# R3S602.net
KiCad netlist of a schematic drawn in Altium Designer
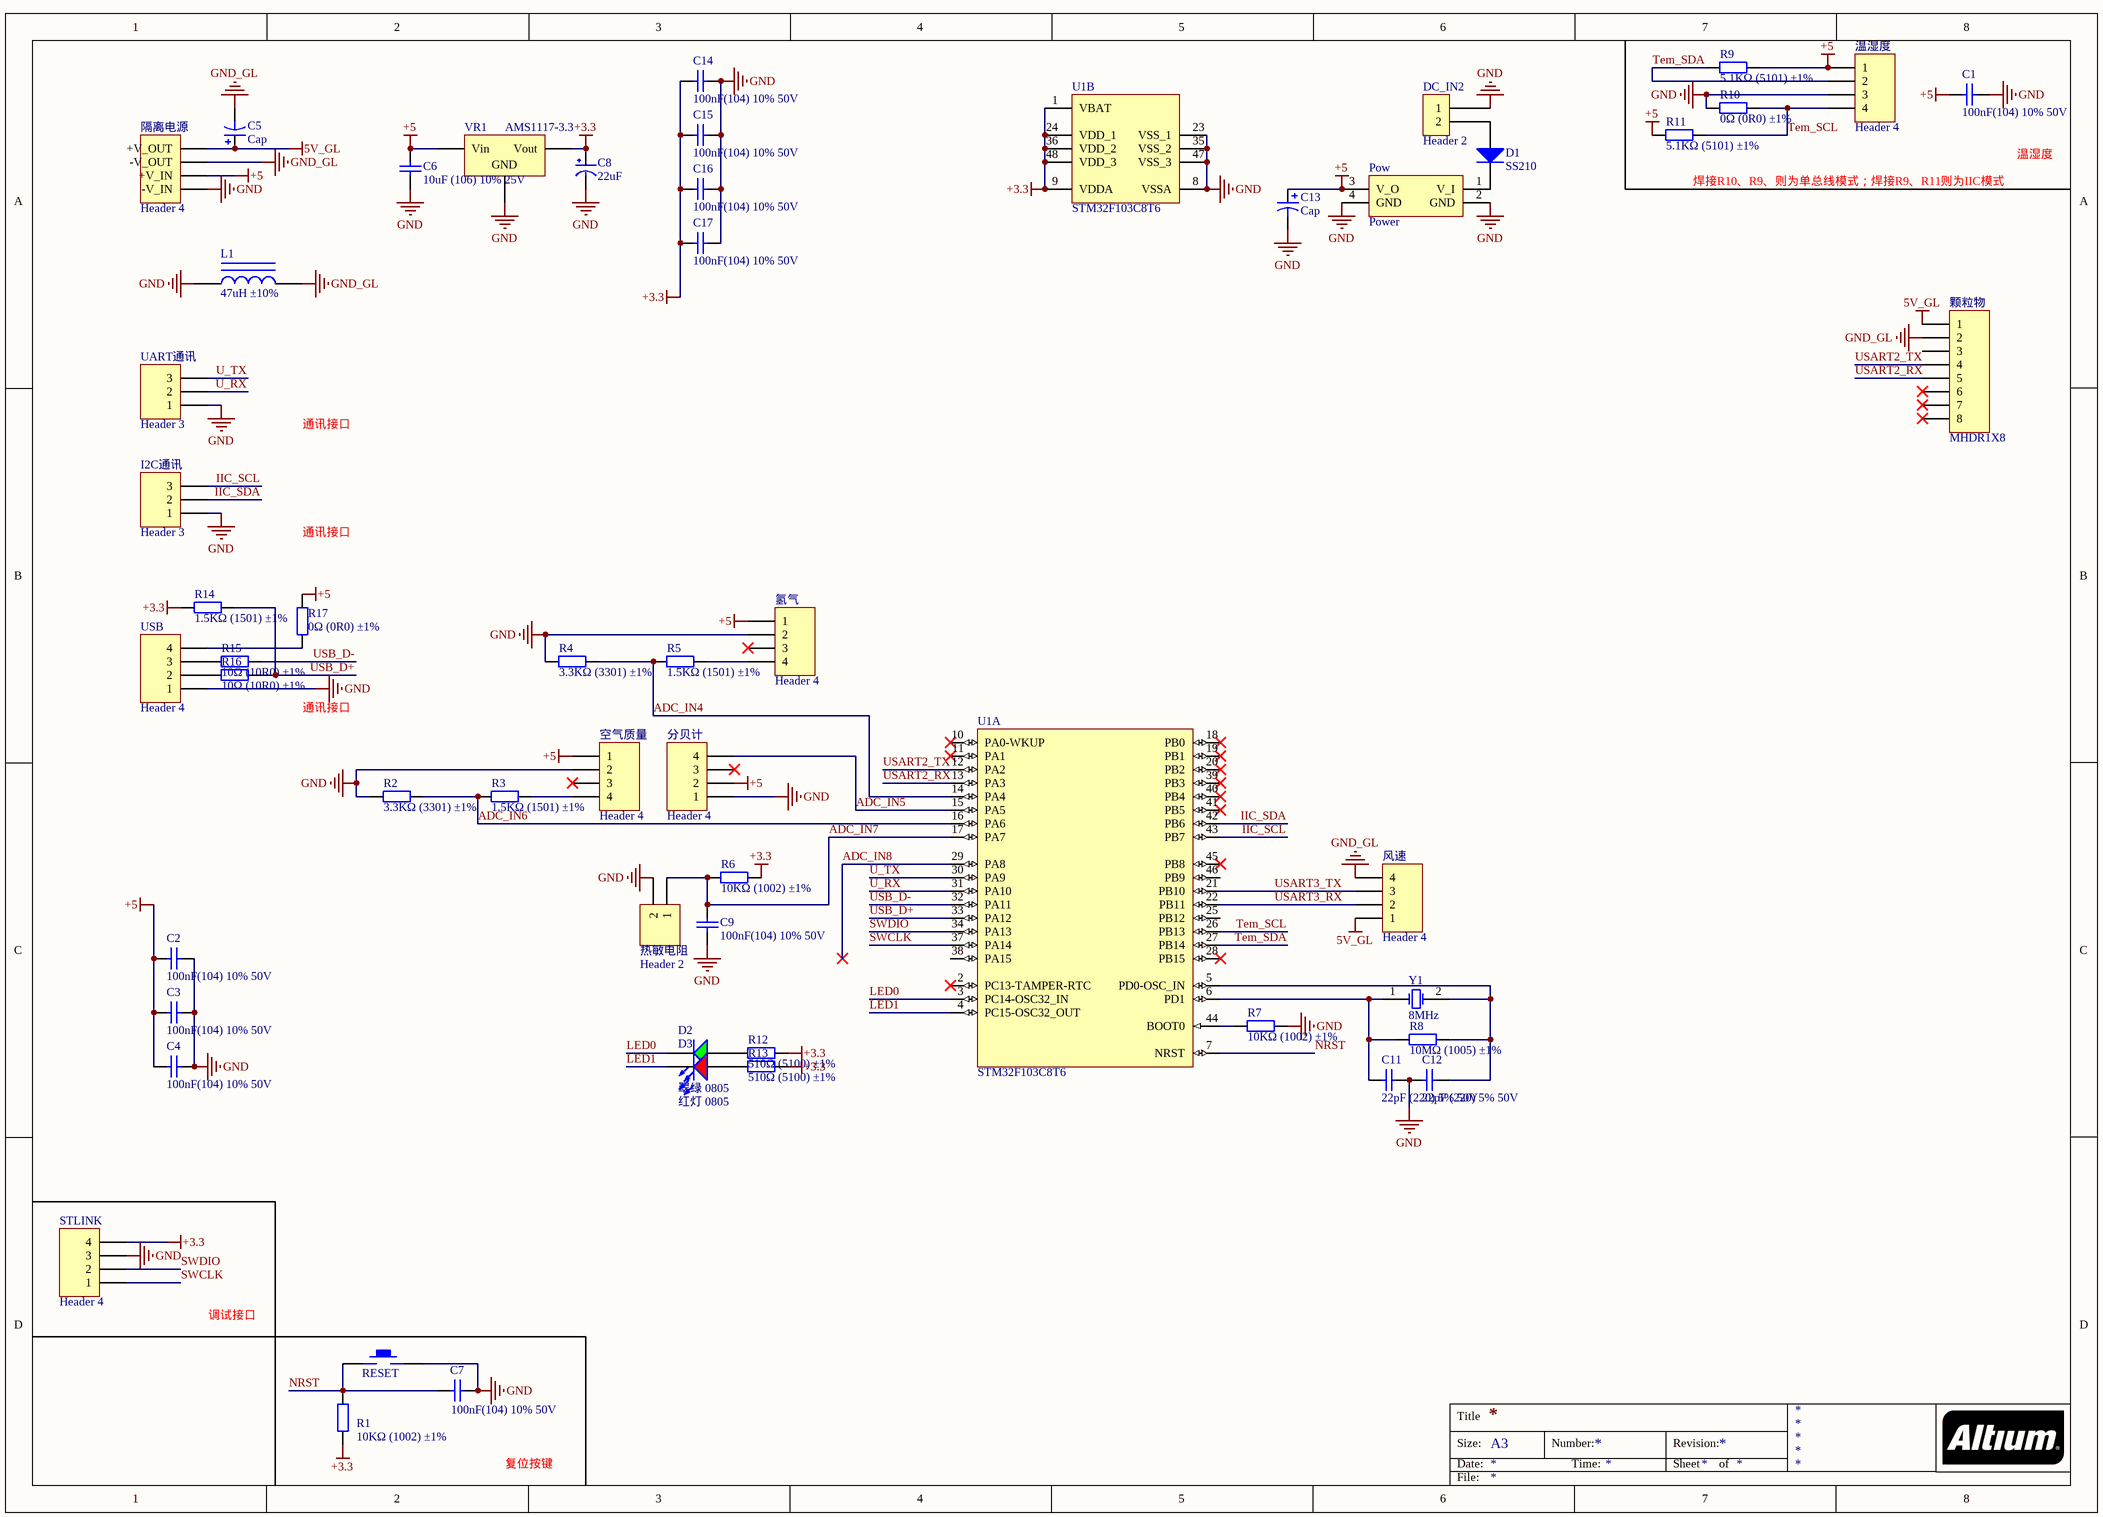
[diagram p0: R3S602.SchDoc]

(export (version "E")
  (design (tool "Eeschema 10.0.6"))
  (components
    (comp (ref "C1")
      (value "100nF(104) 10% 50V")
      (footprint "LC-0805_C")
      (description "贴片电容")
      (libsource (lib "Miscellaneous Devices LC") (part "0805 100nF(104) 10% 50V"))
    )
    (comp (ref "C2")
      (value "100nF(104) 10% 50V")
      (footprint "LC-0805_C")
      (description "贴片电容")
      (libsource (lib "Miscellaneous Devices LC") (part "0805 100nF(104) 10% 50V"))
    )
    (comp (ref "C3")
      (value "100nF(104) 10% 50V")
      (footprint "LC-0805_C")
      (description "贴片电容")
      (libsource (lib "Miscellaneous Devices LC") (part "0805 100nF(104) 10% 50V"))
    )
    (comp (ref "C4")
      (value "100nF(104) 10% 50V")
      (footprint "LC-0805_C")
      (description "贴片电容")
      (libsource (lib "Miscellaneous Devices LC") (part "0805 100nF(104) 10% 50V"))
    )
    (comp (ref "C5")
      (value "Cap")
      (footprint "CAP-DIP-3.5")
      (description "Cap_DIP")
      (libsource (lib "AD_Chip_Y") (part "Cap_DIP"))
    )
    (comp (ref "C6")
      (value "10uF (106) 10% 25V")
      (footprint "LC-0805_C")
      (description "贴片电容")
      (libsource (lib "Miscellaneous Devices LC") (part "0805 10uF (106) 10% 25V"))
    )
    (comp (ref "C7")
      (value "100nF(104) 10% 50V")
      (footprint "LC-0805_C")
      (description "贴片电容")
      (libsource (lib "Miscellaneous Devices LC") (part "0805 100nF(104) 10% 50V"))
    )
    (comp (ref "C8")
      (value "22uF")
      (footprint "CC6.56.5")
      (libsource (lib "Explorer STM32F407封装库") (part "CAP"))
    )
    (comp (ref "C9")
      (value "100nF(104) 10% 50V")
      (footprint "LC-0805_C")
      (description "贴片电容")
      (libsource (lib "Miscellaneous Devices LC") (part "0805 100nF(104) 10% 50V"))
    )
    (comp (ref "C11")
      (value "22pF (220) 5% 50V")
      (footprint "LC-0805_C")
      (description "贴片电容")
      (libsource (lib "Miscellaneous Devices LC") (part "0805 22pF (220) 5% 50V"))
    )
    (comp (ref "C12")
      (value "22pF (220) 5% 50V")
      (footprint "LC-0805_C")
      (description "贴片电容")
      (libsource (lib "Miscellaneous Devices LC") (part "0805 22pF (220) 5% 50V"))
    )
    (comp (ref "C13")
      (value "Cap")
      (footprint "CAP-DIP-3.5")
      (description "Cap_DIP")
      (libsource (lib "AD_Chip_Y") (part "Cap_DIP"))
    )
    (comp (ref "C14")
      (value "100nF(104) 10% 50V")
      (footprint "LC-0805_C")
      (description "贴片电容")
      (libsource (lib "Miscellaneous Devices LC") (part "0805 100nF(104) 10% 50V"))
    )
    (comp (ref "C15")
      (value "100nF(104) 10% 50V")
      (footprint "LC-0805_C")
      (description "贴片电容")
      (libsource (lib "Miscellaneous Devices LC") (part "0805 100nF(104) 10% 50V"))
    )
    (comp (ref "C16")
      (value "100nF(104) 10% 50V")
      (footprint "LC-0805_C")
      (description "贴片电容")
      (libsource (lib "Miscellaneous Devices LC") (part "0805 100nF(104) 10% 50V"))
    )
    (comp (ref "C17")
      (value "100nF(104) 10% 50V")
      (footprint "LC-0805_C")
      (description "贴片电容")
      (libsource (lib "Miscellaneous Devices LC") (part "0805 100nF(104) 10% 50V"))
    )
    (comp (ref "D1")
      (value "SS210")
      (footprint "LC-SMA(DO-214AC)_S1")
      (description "二极管")
      (libsource (lib "Miscellaneous Devices LC") (part "SMA(DO-214AC) SS210"))
    )
    (comp (ref "D2")
      (value "翠绿 0805")
      (footprint "LC-0805_LED_S1")
      (description "发光二极管")
      (libsource (lib "Miscellaneous Devices LC") (part "0805 翠绿"))
    )
    (comp (ref "D3")
      (value "红灯 0805")
      (footprint "LC-0805_LED_S1")
      (description "发光二极管")
      (libsource (lib "Miscellaneous Devices LC") (part "0805 红灯"))
    )
    (comp (ref "DC_IN2")
      (value "Header 2")
      (footprint "VH-2A - Circle Hole")
      (description "贴片2p座")
      (libsource (lib "AD_Chip_Y") (part "Header 2"))
    )
    (comp (ref "I2C通讯")
      (value "Header 3")
      (footprint "HDR1X3")
      (description "Header, 3-Pin")
      (fields (field (name "PUBLISHER") "Altium Limited"))
      (libsource (lib "Miscellaneous Connectors") (part "Header 3"))
    )
    (comp (ref "L1")
      (value "47uH ±10%")
      (footprint "LC-0805_L")
      (description "贴片电感")
      (libsource (lib "Miscellaneous Devices LC") (part "0805 47uH 10%"))
    )
    (comp (ref "Pow")
      (value "Power")
      (footprint "Power_Model")
      (libsource (lib "AD_Chip_Y") (part "Power_Model"))
    )
    (comp (ref "R1")
      (value "10KΩ (1002) ±1%")
      (footprint "LC-0805_R")
      (description "贴片电阻")
      (libsource (lib "") (part "0805 10KΩ (1002) 1%_2"))
    )
    (comp (ref "R2")
      (value "3.3KΩ (3301) ±1%")
      (footprint "LC-0805_R")
      (description "贴片电阻")
      (libsource (lib "Miscellaneous Devices LC") (part "0805 3.3KΩ (3301) 1%"))
    )
    (comp (ref "R3")
      (value "1.5KΩ (1501) ±1%")
      (footprint "LC-0805_R")
      (description "贴片电阻")
      (libsource (lib "Miscellaneous Devices LC") (part "0805 1.5KΩ (1501) 1%"))
    )
    (comp (ref "R4")
      (value "3.3KΩ (3301) ±1%")
      (footprint "LC-0805_R")
      (description "贴片电阻")
      (libsource (lib "Miscellaneous Devices LC") (part "0805 3.3KΩ (3301) 1%"))
    )
    (comp (ref "R5")
      (value "1.5KΩ (1501) ±1%")
      (footprint "LC-0805_R")
      (description "贴片电阻")
      (libsource (lib "Miscellaneous Devices LC") (part "0805 1.5KΩ (1501) 1%"))
    )
    (comp (ref "R6")
      (value "10KΩ (1002) ±1%")
      (footprint "LC-0805_R")
      (description "贴片电阻")
      (libsource (lib "Miscellaneous Devices LC") (part "0805 10KΩ (1002) 1%"))
    )
    (comp (ref "R7")
      (value "10KΩ (1002) ±1%")
      (footprint "LC-0805_R")
      (description "贴片电阻")
      (libsource (lib "") (part "0805 10KΩ (1002) 1%_1"))
    )
    (comp (ref "R8")
      (value "10MΩ (1005) ±1%")
      (footprint "LC-0805_R")
      (description "贴片电阻")
      (libsource (lib "Miscellaneous Devices LC") (part "0805 10MΩ (1005) 1%"))
    )
    (comp (ref "R9")
      (value "5.1KΩ (5101) ±1%")
      (footprint "LC-0805_R")
      (description "贴片电阻")
      (libsource (lib "Miscellaneous Devices LC") (part "0805 5.1KΩ (5101) 1%"))
    )
    (comp (ref "R10")
      (value "0Ω (0R0) ±1%")
      (footprint "LC-0603_R")
      (description "贴片电阻")
      (libsource (lib "Miscellaneous Devices LC") (part "0603 0Ω (0R0) 1%"))
    )
    (comp (ref "R11")
      (value "5.1KΩ (5101) ±1%")
      (footprint "LC-0805_R")
      (description "贴片电阻")
      (libsource (lib "Miscellaneous Devices LC") (part "0805 5.1KΩ (5101) 1%"))
    )
    (comp (ref "R12")
      (value "510Ω (5100) ±1%")
      (footprint "LC-0805_R")
      (description "贴片电阻")
      (libsource (lib "Miscellaneous Devices LC") (part "0805 510Ω (5100) 1%"))
    )
    (comp (ref "R13")
      (value "510Ω (5100) ±1%")
      (footprint "LC-0805_R")
      (description "贴片电阻")
      (libsource (lib "Miscellaneous Devices LC") (part "0805 510Ω (5100) 1%"))
    )
    (comp (ref "R14")
      (value "1.5KΩ (1501) ±1%")
      (footprint "LC-0805_R")
      (description "贴片电阻")
      (libsource (lib "") (part "0805 1.5KΩ (1501) 1%_1"))
    )
    (comp (ref "R15")
      (value "10Ω (10R0) ±1%")
      (footprint "LC-0805_R")
      (description "贴片电阻")
      (libsource (lib "Miscellaneous Devices LC") (part "0805 10Ω (10R0) 1%"))
    )
    (comp (ref "R16")
      (value "10Ω (10R0) ±1%")
      (footprint "LC-0805_R")
      (description "贴片电阻")
      (libsource (lib "Miscellaneous Devices LC") (part "0805 10Ω (10R0) 1%"))
    )
    (comp (ref "R17")
      (value "0Ω (0R0) ±1%")
      (footprint "LC-0603_R")
      (description "贴片电阻")
      (libsource (lib "") (part "0603 0Ω (0R0) 1%_1"))
    )
    (comp (ref "RESET") (value "KEY_M") (footprint "KEY_M") (libsource (lib "AD_Chip_Y") (part "KEY_M")))
    (comp (ref "STLINK")
      (value "Header 4")
      (footprint "HDR1X4")
      (description "Header, 4-Pin")
      (fields (field (name "PUBLISHER") "Altium Limited"))
      (libsource (lib "Miscellaneous Connectors") (part "Header 4"))
    )
    (comp (ref "U1")
      (value "STM32F103C8T6")
      (footprint "LC-LQFP-48_7x7x05P")
      (description "ARM")
      (libsource (lib "Miscellaneous Devices LC") (part "STM32F103C8T6"))
    )
    (comp (ref "UART通讯")
      (value "Header 3")
      (footprint "HDR1X3")
      (description "Header, 3-Pin")
      (fields (field (name "PUBLISHER") "Altium Limited"))
      (libsource (lib "Miscellaneous Connectors") (part "Header 3"))
    )
    (comp (ref "USB")
      (value "Header 4")
      (footprint "HDR1X4")
      (description "Header, 4-Pin")
      (fields (field (name "PUBLISHER") "Altium Limited"))
      (libsource (lib "Miscellaneous Connectors") (part "Header 4"))
    )
    (comp (ref "VR1")
      (value "AMS1117-3.3")
      (footprint "LC-SOT-223")
      (description "低压差线性稳压(LDO)")
      (libsource (lib "Miscellaneous Devices LC") (part "SOT-223 AMS1117-3.3"))
    )
    (comp (ref "Y1")
      (value "8MHz")
      (footprint "XTAL_US")
      (description "Crystal Oscillator")
      (fields (field (name "PUBLISHER") "Altium Limited"))
      (libsource (lib "Explorer STM32F407封装库") (part "XTAL"))
    )
    (comp (ref "分贝计")
      (value "Header 4")
      (footprint "HDR1X4")
      (description "Header, 4-Pin")
      (fields (field (name "PUBLISHER") "Altium Limited"))
      (libsource (lib "Miscellaneous Connectors") (part "Header 4"))
    )
    (comp (ref "氢气")
      (value "Header 4")
      (footprint "HDR1X4")
      (description "Header, 4-Pin")
      (fields (field (name "PUBLISHER") "Altium Limited"))
      (libsource (lib "") (part "Header 4_1"))
    )
    (comp (ref "温湿度")
      (value "Header 4")
      (footprint "HDR1X4")
      (description "Header, 4-Pin")
      (fields (field (name "PUBLISHER") "Altium Limited"))
      (libsource (lib "") (part "Header 4_1"))
    )
    (comp (ref "热敏电阻")
      (value "Header 2")
      (footprint "HDR1X2")
      (description "Header, 2-Pin")
      (fields (field (name "PUBLISHER") "Altium Limited"))
      (libsource (lib "Miscellaneous Connectors") (part "Header 2"))
    )
    (comp (ref "空气质量")
      (value "Header 4")
      (footprint "HDR1X4")
      (description "Header, 4-Pin")
      (fields (field (name "PUBLISHER") "Altium Limited"))
      (libsource (lib "") (part "Header 4_1"))
    )
    (comp (ref "隔离电源")
      (value "Header 4")
      (footprint "HDR1X4")
      (description "Header, 4-Pin")
      (fields (field (name "PUBLISHER") "Altium Limited"))
      (libsource (lib "Miscellaneous Connectors") (part "Header 4"))
    )
    (comp (ref "颗粒物")
      (value "MHDR1X8")
      (footprint "MHDR1X8")
      (description "Header, 8-Pin")
      (fields (field (name "PUBLISHER") "Altium Limited"))
      (libsource (lib "Miscellaneous Connectors") (part "MHDR1X8"))
    )
    (comp (ref "风速")
      (value "Header 4")
      (footprint "HDR1X4")
      (description "Header, 4-Pin")
      (fields (field (name "PUBLISHER") "Altium Limited"))
      (libsource (lib "") (part "Header 4_2"))
    )
  )
  (nets
    (net (code "1") (name "+3.3") (class "Default")
      (node (ref "C14") (pin "2") (pinfunction "2_2") (pintype "passive"))
      (node (ref "C15") (pin "2") (pinfunction "2_2") (pintype "passive"))
      (node (ref "C16") (pin "2") (pinfunction "2_2") (pintype "passive"))
      (node (ref "C17") (pin "2") (pinfunction "2_2") (pintype "passive"))
      (node (ref "C8") (pin "1") (pinfunction "VCC_1") (pintype "passive"))
      (node (ref "R1") (pin "1") (pinfunction "1_1") (pintype "passive"))
      (node (ref "R12") (pin "2") (pinfunction "2_2") (pintype "passive"))
      (node (ref "R13") (pin "2") (pinfunction "2_2") (pintype "passive"))
      (node (ref "R14") (pin "2") (pinfunction "2_2") (pintype "passive"))
      (node (ref "R6") (pin "1") (pinfunction "1_1") (pintype "passive"))
      (node (ref "STLINK") (pin "4") (pinfunction "+V_OUT_4") (pintype "passive"))
      (node (ref "U1") (pin "1") (pinfunction "VBAT_1") (pintype "power_in"))
      (node (ref "U1") (pin "24") (pinfunction "VDD_1_24") (pintype "power_in"))
      (node (ref "U1") (pin "36") (pinfunction "VDD_2_36") (pintype "power_in"))
      (node (ref "U1") (pin "48") (pinfunction "VDD_3_48") (pintype "power_in"))
      (node (ref "U1") (pin "9") (pinfunction "VDDA_9") (pintype "power_in"))
      (node (ref "VR1") (pin "2") (pinfunction "Vout_2") (pintype "passive"))
    )
    (net (code "2") (name "+5") (class "Default")
      (node (ref "C1") (pin "2") (pinfunction "2_2") (pintype "passive"))
      (node (ref "C13") (pin "1") (pinfunction "1_1") (pintype "passive"))
      (node (ref "C2") (pin "1") (pinfunction "1_1") (pintype "passive"))
      (node (ref "C3") (pin "1") (pinfunction "1_1") (pintype "passive"))
      (node (ref "C4") (pin "1") (pinfunction "1_1") (pintype "passive"))
      (node (ref "C6") (pin "2") (pinfunction "2_2") (pintype "passive"))
      (node (ref "Pow") (pin "3") (pinfunction "V_O_3") (pintype "passive"))
      (node (ref "R11") (pin "1") (pinfunction "1_1") (pintype "passive"))
      (node (ref "R17") (pin "2") (pinfunction "2_2") (pintype "passive"))
      (node (ref "R9") (pin "2") (pinfunction "2_2") (pintype "passive"))
      (node (ref "VR1") (pin "3") (pinfunction "Vin_3") (pintype "passive"))
      (node (ref "分贝计") (pin "2") (pinfunction "+V_IN_2") (pintype "passive"))
      (node (ref "氢气") (pin "1") (pinfunction "1_1") (pintype "passive"))
      (node (ref "温湿度") (pin "1") (pinfunction "1_1") (pintype "passive"))
      (node (ref "空气质量") (pin "1") (pinfunction "1_1") (pintype "passive"))
      (node (ref "隔离电源") (pin "2") (pinfunction "+V_IN_2") (pintype "passive"))
    )
    (net (code "3") (name "/ADC_IN4") (class "Default")
      (node (ref "R4") (pin "2") (pinfunction "2_2") (pintype "passive"))
      (node (ref "R5") (pin "1") (pinfunction "1_1") (pintype "passive"))
      (node (ref "U1") (pin "14") (pinfunction "PA4_14") (pintype "bidirectional"))
    )
    (net (code "4") (name "/ADC_IN5") (class "Default")
      (node (ref "U1") (pin "15") (pinfunction "PA5_15") (pintype "bidirectional"))
      (node (ref "分贝计") (pin "4") (pinfunction "+V_OUT_4") (pintype "passive"))
    )
    (net (code "5") (name "/ADC_IN6") (class "Default")
      (node (ref "R2") (pin "2") (pinfunction "2_2") (pintype "passive"))
      (node (ref "R3") (pin "1") (pinfunction "1_1") (pintype "passive"))
      (node (ref "U1") (pin "16") (pinfunction "PA6_16") (pintype "bidirectional"))
    )
    (net (code "6") (name "/ADC_IN7") (class "Default")
      (node (ref "C9") (pin "2") (pinfunction "2_2") (pintype "passive"))
      (node (ref "R6") (pin "2") (pinfunction "2_2") (pintype "passive"))
      (node (ref "U1") (pin "17") (pinfunction "PA7_17") (pintype "bidirectional"))
      (node (ref "热敏电阻") (pin "1") (pinfunction "1_1") (pintype "passive"))
    )
    (net (code "7") (name "/ADC_IN8") (class "Default")
      (node (ref "U1") (pin "29") (pinfunction "PA8_29") (pintype "bidirectional+no_connect"))
    )
    (net (code "8") (name "/IIC_SCL") (class "Default")
      (node (ref "I2C通讯") (pin "3") (pinfunction "3_3") (pintype "passive"))
      (node (ref "U1") (pin "43") (pinfunction "PB7_43") (pintype "bidirectional"))
    )
    (net (code "9") (name "/IIC_SDA") (class "Default")
      (node (ref "I2C通讯") (pin "2") (pinfunction "2_2") (pintype "passive"))
      (node (ref "U1") (pin "42") (pinfunction "PB6_42") (pintype "bidirectional"))
    )
    (net (code "10") (name "/LED0") (class "Default")
      (node (ref "D2") (pin "K") (pinfunction "K_K") (pintype "passive"))
      (node (ref "U1") (pin "3") (pinfunction "PC14-OSC32_IN_3") (pintype "bidirectional"))
    )
    (net (code "11") (name "/LED1") (class "Default")
      (node (ref "D3") (pin "K") (pinfunction "K_K") (pintype "passive"))
      (node (ref "U1") (pin "4") (pinfunction "PC15-OSC32_OUT_4") (pintype "bidirectional"))
    )
    (net (code "12") (name "/NRST") (class "Default")
      (node (ref "C7") (pin "2") (pinfunction "2_2") (pintype "passive"))
      (node (ref "R1") (pin "2") (pinfunction "2_2") (pintype "passive"))
      (node (ref "RESET") (pin "1") (pinfunction "1_1") (pintype "passive"))
      (node (ref "U1") (pin "7") (pinfunction "NRST_7") (pintype "bidirectional"))
    )
    (net (code "13") (name "/SWCLK") (class "Default")
      (node (ref "STLINK") (pin "1") (pinfunction "-V_IN_1") (pintype "passive"))
      (node (ref "U1") (pin "37") (pinfunction "PA14_37") (pintype "bidirectional"))
    )
    (net (code "14") (name "/SWDIO") (class "Default")
      (node (ref "STLINK") (pin "2") (pinfunction "+V_IN_2") (pintype "passive"))
      (node (ref "U1") (pin "34") (pinfunction "PA13_34") (pintype "bidirectional"))
    )
    (net (code "15") (name "/Tem_SCL") (class "Default")
      (node (ref "R10") (pin "2") (pinfunction "2_2") (pintype "passive"))
      (node (ref "R11") (pin "2") (pinfunction "2_2") (pintype "passive"))
      (node (ref "U1") (pin "26") (pinfunction "PB13_26") (pintype "bidirectional"))
      (node (ref "温湿度") (pin "4") (pinfunction "4_4") (pintype "passive"))
    )
    (net (code "16") (name "/Tem_SDA") (class "Default")
      (node (ref "R9") (pin "1") (pinfunction "1_1") (pintype "passive"))
      (node (ref "U1") (pin "27") (pinfunction "PB14_27") (pintype "bidirectional"))
      (node (ref "温湿度") (pin "2") (pinfunction "2_2") (pintype "passive"))
    )
    (net (code "17") (name "/USART2_RX") (class "Default")
      (node (ref "U1") (pin "13") (pinfunction "PA3_13") (pintype "bidirectional"))
      (node (ref "颗粒物") (pin "5") (pinfunction "5_5") (pintype "passive"))
    )
    (net (code "18") (name "/USART2_TX") (class "Default")
      (node (ref "U1") (pin "12") (pinfunction "PA2_12") (pintype "bidirectional"))
      (node (ref "颗粒物") (pin "4") (pinfunction "4_4") (pintype "passive"))
    )
    (net (code "19") (name "/USART3_RX") (class "Default")
      (node (ref "U1") (pin "22") (pinfunction "PB11_22") (pintype "bidirectional"))
      (node (ref "风速") (pin "2") (pinfunction "2_2") (pintype "passive"))
    )
    (net (code "20") (name "/USART3_TX") (class "Default")
      (node (ref "U1") (pin "21") (pinfunction "PB10_21") (pintype "bidirectional"))
      (node (ref "风速") (pin "3") (pinfunction "3_3") (pintype "passive"))
    )
    (net (code "21") (name "/USB_D+") (class "Default")
      (node (ref "R14") (pin "1") (pinfunction "1_1") (pintype "passive"))
      (node (ref "R16") (pin "2") (pinfunction "2_2") (pintype "passive"))
      (node (ref "U1") (pin "33") (pinfunction "PA12_33") (pintype "bidirectional"))
    )
    (net (code "22") (name "/USB_D-") (class "Default")
      (node (ref "R15") (pin "2") (pinfunction "2_2") (pintype "passive"))
      (node (ref "U1") (pin "32") (pinfunction "PA11_32") (pintype "bidirectional"))
    )
    (net (code "23") (name "/U_RX") (class "Default")
      (node (ref "U1") (pin "31") (pinfunction "PA10_31") (pintype "bidirectional"))
      (node (ref "UART通讯") (pin "2") (pinfunction "2_2") (pintype "passive"))
    )
    (net (code "24") (name "/U_TX") (class "Default")
      (node (ref "U1") (pin "30") (pinfunction "PA9_30") (pintype "bidirectional"))
      (node (ref "UART通讯") (pin "3") (pinfunction "3_3") (pintype "passive"))
    )
    (net (code "25") (name "5V_GL") (class "Default")
      (node (ref "C5") (pin "1") (pinfunction "1_1") (pintype "passive"))
      (node (ref "隔离电源") (pin "4") (pinfunction "+V_OUT_4") (pintype "passive"))
      (node (ref "颗粒物") (pin "1") (pinfunction "1_1") (pintype "passive"))
      (node (ref "风速") (pin "1") (pinfunction "1_1") (pintype "passive"))
    )
    (net (code "26") (name "GND") (class "Default")
      (node (ref "C1") (pin "1") (pinfunction "1_1") (pintype "passive"))
      (node (ref "C11") (pin "2") (pinfunction "2_2") (pintype "passive"))
      (node (ref "C12") (pin "1") (pinfunction "1_1") (pintype "passive"))
      (node (ref "C13") (pin "2") (pinfunction "2_2") (pintype "passive"))
      (node (ref "C14") (pin "1") (pinfunction "1_1") (pintype "passive"))
      (node (ref "C15") (pin "1") (pinfunction "1_1") (pintype "passive"))
      (node (ref "C16") (pin "1") (pinfunction "1_1") (pintype "passive"))
      (node (ref "C17") (pin "1") (pinfunction "1_1") (pintype "passive"))
      (node (ref "C2") (pin "2") (pinfunction "2_2") (pintype "passive"))
      (node (ref "C3") (pin "2") (pinfunction "2_2") (pintype "passive"))
      (node (ref "C4") (pin "2") (pinfunction "2_2") (pintype "passive"))
      (node (ref "C6") (pin "1") (pinfunction "1_1") (pintype "passive"))
      (node (ref "C7") (pin "1") (pinfunction "1_1") (pintype "passive"))
      (node (ref "C8") (pin "2") (pinfunction "GND_2") (pintype "passive"))
      (node (ref "C9") (pin "1") (pinfunction "1_1") (pintype "passive"))
      (node (ref "DC_IN2") (pin "1") (pinfunction "1_1") (pintype "passive"))
      (node (ref "I2C通讯") (pin "1") (pinfunction "1_1") (pintype "passive"))
      (node (ref "L1") (pin "1") (pinfunction "1_1") (pintype "passive"))
      (node (ref "Pow") (pin "2") (pinfunction "GND_2") (pintype "passive"))
      (node (ref "Pow") (pin "4") (pinfunction "GND_4") (pintype "passive"))
      (node (ref "R10") (pin "1") (pinfunction "1_1") (pintype "passive"))
      (node (ref "R2") (pin "1") (pinfunction "1_1") (pintype "passive"))
      (node (ref "R4") (pin "1") (pinfunction "1_1") (pintype "passive"))
      (node (ref "R7") (pin "2") (pinfunction "2_2") (pintype "passive"))
      (node (ref "RESET") (pin "2") (pinfunction "2_2") (pintype "passive"))
      (node (ref "STLINK") (pin "3") (pinfunction "-V_OUT_3") (pintype "passive"))
      (node (ref "U1") (pin "23") (pinfunction "VSS_1_23") (pintype "power_in"))
      (node (ref "U1") (pin "35") (pinfunction "VSS_2_35") (pintype "power_in"))
      (node (ref "U1") (pin "47") (pinfunction "VSS_3_47") (pintype "power_in"))
      (node (ref "U1") (pin "8") (pinfunction "VSSA_8") (pintype "power_in"))
      (node (ref "UART通讯") (pin "1") (pinfunction "1_1") (pintype "passive"))
      (node (ref "USB") (pin "1") (pinfunction "-V_IN_1") (pintype "passive"))
      (node (ref "VR1") (pin "1") (pinfunction "GND_1") (pintype "passive"))
      (node (ref "分贝计") (pin "1") (pinfunction "-V_IN_1") (pintype "passive"))
      (node (ref "氢气") (pin "2") (pinfunction "2_2") (pintype "passive"))
      (node (ref "温湿度") (pin "3") (pinfunction "3_3") (pintype "passive"))
      (node (ref "热敏电阻") (pin "2") (pinfunction "2_2") (pintype "passive"))
      (node (ref "空气质量") (pin "2") (pinfunction "2_2") (pintype "passive"))
      (node (ref "隔离电源") (pin "1") (pinfunction "-V_IN_1") (pintype "passive"))
    )
    (net (code "27") (name "GND_GL") (class "Default")
      (node (ref "C5") (pin "2") (pinfunction "2_2") (pintype "passive"))
      (node (ref "L1") (pin "2") (pinfunction "2_2") (pintype "passive"))
      (node (ref "隔离电源") (pin "3") (pinfunction "-V_OUT_3") (pintype "passive"))
      (node (ref "颗粒物") (pin "2") (pinfunction "2_2") (pintype "passive"))
      (node (ref "风速") (pin "4") (pinfunction "4_4") (pintype "passive"))
    )
    (net (code "28") (name "Net-(D1-A)") (class "Default")
      (node (ref "D1") (pin "1") (pinfunction "A_1") (pintype "passive"))
      (node (ref "DC_IN2") (pin "2") (pinfunction "2_2") (pintype "passive"))
    )
    (net (code "29") (name "Net-(D1-K)") (class "Default")
      (node (ref "D1") (pin "2") (pinfunction "K_2") (pintype "passive"))
      (node (ref "Pow") (pin "1") (pinfunction "V_I_1") (pintype "passive"))
    )
    (net (code "30") (name "Net-(D2-PadA)") (class "Default")
      (node (ref "D2") (pin "A") (pinfunction "A_A") (pintype "passive"))
      (node (ref "R12") (pin "1") (pinfunction "1_1") (pintype "passive"))
    )
    (net (code "31") (name "Net-(D3-PadA)") (class "Default")
      (node (ref "D3") (pin "A") (pinfunction "A_A") (pintype "passive"))
      (node (ref "R13") (pin "1") (pinfunction "1_1") (pintype "passive"))
    )
    (net (code "32") (name "Net-(R3-Pad2)") (class "Default")
      (node (ref "R3") (pin "2") (pinfunction "2_2") (pintype "passive"))
      (node (ref "空气质量") (pin "4") (pinfunction "4_4") (pintype "passive"))
    )
    (net (code "33") (name "Net-(R5-Pad2)") (class "Default")
      (node (ref "R5") (pin "2") (pinfunction "2_2") (pintype "passive"))
      (node (ref "氢气") (pin "4") (pinfunction "4_4") (pintype "passive"))
    )
    (net (code "34") (name "Net-(U1A-BOOT0)") (class "Default")
      (node (ref "R7") (pin "1") (pinfunction "1_1") (pintype "passive"))
      (node (ref "U1") (pin "44") (pinfunction "BOOT0_44") (pintype "input"))
    )
    (net (code "35") (name "Net-(U1A-PD0-OSC_IN)") (class "Default")
      (node (ref "C12") (pin "2") (pinfunction "2_2") (pintype "passive"))
      (node (ref "R8") (pin "2") (pinfunction "2_2") (pintype "passive"))
      (node (ref "U1") (pin "5") (pinfunction "PD0-OSC_IN_5") (pintype "bidirectional"))
      (node (ref "Y1") (pin "2") (pinfunction "OSC2_2") (pintype "passive"))
    )
    (net (code "36") (name "Net-(U1A-PD1)") (class "Default")
      (node (ref "C11") (pin "1") (pinfunction "1_1") (pintype "passive"))
      (node (ref "R8") (pin "1") (pinfunction "1_1") (pintype "passive"))
      (node (ref "U1") (pin "6") (pinfunction "PD1_6") (pintype "bidirectional"))
      (node (ref "Y1") (pin "1") (pinfunction "OSC1_1") (pintype "passive"))
    )
    (net (code "37") (name "Net-(USB-+V_IN)") (class "Default")
      (node (ref "R16") (pin "1") (pinfunction "1_1") (pintype "passive"))
      (node (ref "USB") (pin "2") (pinfunction "+V_IN_2") (pintype "passive"))
    )
    (net (code "38") (name "Net-(USB-+V_OUT)") (class "Default")
      (node (ref "R17") (pin "1") (pinfunction "1_1") (pintype "passive"))
      (node (ref "USB") (pin "4") (pinfunction "+V_OUT_4") (pintype "passive"))
    )
    (net (code "39") (name "Net-(USB--V_OUT)") (class "Default")
      (node (ref "R15") (pin "1") (pinfunction "1_1") (pintype "passive"))
      (node (ref "USB") (pin "3") (pinfunction "-V_OUT_3") (pintype "passive"))
    )
    (net (code "40") (name "unconnected-(U1A-PA0-WKUP-Pad10)") (class "Default")
      (node (ref "U1") (pin "10") (pinfunction "PA0-WKUP_10") (pintype "bidirectional+no_connect"))
    )
    (net (code "41") (name "unconnected-(U1A-PA1-Pad11)") (class "Default")
      (node (ref "U1") (pin "11") (pinfunction "PA1_11") (pintype "bidirectional+no_connect"))
    )
    (net (code "42") (name "unconnected-(U1A-PA15-Pad38)") (class "Default")
      (node (ref "U1") (pin "38") (pinfunction "PA15_38") (pintype "bidirectional"))
    )
    (net (code "43") (name "unconnected-(U1A-PB0-Pad18)") (class "Default")
      (node (ref "U1") (pin "18") (pinfunction "PB0_18") (pintype "bidirectional+no_connect"))
    )
    (net (code "44") (name "unconnected-(U1A-PB1-Pad19)") (class "Default")
      (node (ref "U1") (pin "19") (pinfunction "PB1_19") (pintype "bidirectional+no_connect"))
    )
    (net (code "45") (name "unconnected-(U1A-PB2-Pad20)") (class "Default")
      (node (ref "U1") (pin "20") (pinfunction "PB2_20") (pintype "bidirectional+no_connect"))
    )
    (net (code "46") (name "unconnected-(U1A-PB3-Pad39)") (class "Default")
      (node (ref "U1") (pin "39") (pinfunction "PB3_39") (pintype "bidirectional+no_connect"))
    )
    (net (code "47") (name "unconnected-(U1A-PB4-Pad40)") (class "Default")
      (node (ref "U1") (pin "40") (pinfunction "PB4_40") (pintype "bidirectional+no_connect"))
    )
    (net (code "48") (name "unconnected-(U1A-PB5-Pad41)") (class "Default")
      (node (ref "U1") (pin "41") (pinfunction "PB5_41") (pintype "bidirectional+no_connect"))
    )
    (net (code "49") (name "unconnected-(U1A-PB8-Pad45)") (class "Default")
      (node (ref "U1") (pin "45") (pinfunction "PB8_45") (pintype "bidirectional+no_connect"))
    )
    (net (code "50") (name "unconnected-(U1A-PB9-Pad46)") (class "Default")
      (node (ref "U1") (pin "46") (pinfunction "PB9_46") (pintype "bidirectional"))
    )
    (net (code "51") (name "unconnected-(U1A-PB12-Pad25)") (class "Default")
      (node (ref "U1") (pin "25") (pinfunction "PB12_25") (pintype "bidirectional"))
    )
    (net (code "52") (name "unconnected-(U1A-PB15-Pad28)") (class "Default")
      (node (ref "U1") (pin "28") (pinfunction "PB15_28") (pintype "bidirectional+no_connect"))
    )
    (net (code "53") (name "unconnected-(U1A-PC13-TAMPER-RTC-Pad2)") (class "Default")
      (node (ref "U1") (pin "2") (pinfunction "PC13-TAMPER-RTC_2") (pintype "bidirectional+no_connect"))
    )
    (net (code "54") (name "unconnected-(分贝计--V_OUT-Pad3)") (class "Default")
      (node (ref "分贝计") (pin "3") (pinfunction "-V_OUT_3") (pintype "passive+no_connect"))
    )
    (net (code "55") (name "unconnected-(氢气-Pad3)") (class "Default")
      (node (ref "氢气") (pin "3") (pinfunction "3_3") (pintype "passive+no_connect"))
    )
    (net (code "56") (name "unconnected-(空气质量-Pad3)") (class "Default")
      (node (ref "空气质量") (pin "3") (pinfunction "3_3") (pintype "passive+no_connect"))
    )
    (net (code "57") (name "unconnected-(颗粒物-Pad3)") (class "Default")
      (node (ref "颗粒物") (pin "3") (pinfunction "3_3") (pintype "passive"))
    )
    (net (code "58") (name "unconnected-(颗粒物-Pad6)") (class "Default")
      (node (ref "颗粒物") (pin "6") (pinfunction "6_6") (pintype "passive+no_connect"))
    )
    (net (code "59") (name "unconnected-(颗粒物-Pad7)") (class "Default")
      (node (ref "颗粒物") (pin "7") (pinfunction "7_7") (pintype "passive+no_connect"))
    )
    (net (code "60") (name "unconnected-(颗粒物-Pad8)") (class "Default")
      (node (ref "颗粒物") (pin "8") (pinfunction "8_8") (pintype "passive+no_connect"))
    )
  )
)
